# SNES_DRONE_CART.net
KiCad netlist of a schematic drawn in Altium Designer
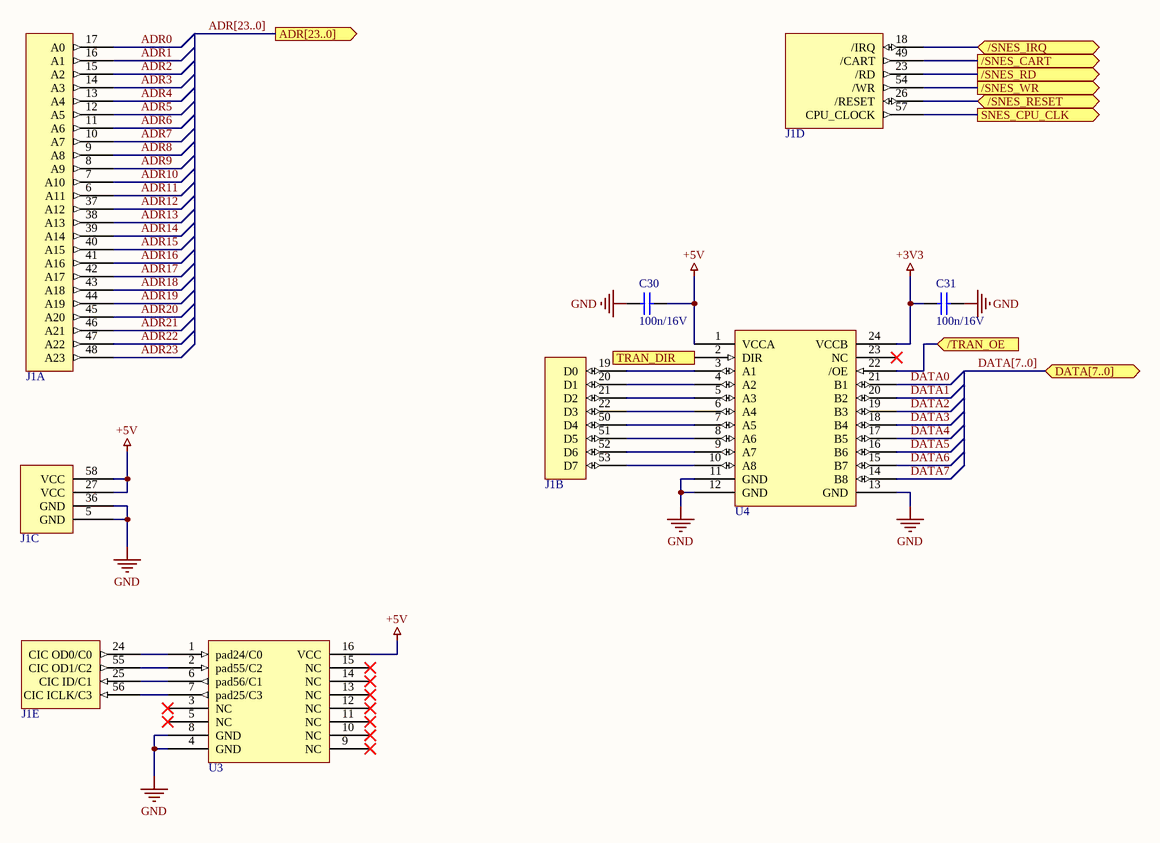
[diagram p0: SNES_DRONE_CART.SchDoc]

(export (version "E")
  (design (tool "Eeschema 10.0.6"))
  (components
    (comp (ref "C30")
      (value "100n/16V")
      (footprint "0402_RES")
      (description "Keramikvielschichtkondensator, SMD, 0.1 µF, 16 V, 0402 [Metrisch 1005], ± 10%, X5R, Baureihe MC")
      (libsource (lib "My_Integrated_Library") (part "Cap_100n_0402"))
    )
    (comp (ref "C31")
      (value "100n/16V")
      (footprint "0402_RES")
      (description "Keramikvielschichtkondensator, SMD, 0.1 µF, 16 V, 0402 [Metrisch 1005], ± 10%, X5R, Baureihe MC")
      (libsource (lib "My_Integrated_Library") (part "Cap_100n_0402"))
    )
    (comp (ref "J1")
      (value "SNES Cartridge Connector")
      (footprint "SNES Cartridge Connector")
      (libsource (lib "My_Schlib") (part "SNES Cartridge Connector"))
    )
    (comp (ref "U3")
      (value "IC_D411A")
      (footprint "DIP16")
      (description "SNES CIC Chip")
      (libsource (lib "My_Integrated_Library") (part "IC_D411A"))
    )
    (comp (ref "U4")
      (value "IC_SN74LVCC3245APWR")
      (footprint "TSSOP24")
      (description "Bus-Transceiver, Produktreihe LVC, 8 Eingänge, 50mA, 7ns, 2.3V bis 5.5V, TSSOP 24")
      (libsource (lib "My_Schlib") (part "IC_SN74LVCC3245APWR"))
    )
  )
  (nets
    (net (code "1") (name "+3V3") (class "Default")
      (node (ref "C31") (pin "1") (pinfunction "1_1") (pintype "passive"))
      (node (ref "U4") (pin "24") (pinfunction "VCCB_24") (pintype "power_in"))
    )
    (net (code "2") (name "+5V") (class "Default")
      (node (ref "C30") (pin "2") (pinfunction "2_2") (pintype "passive"))
      (node (ref "J1") (pin "27") (pinfunction "VCC_27") (pintype "power_in"))
      (node (ref "J1") (pin "58") (pinfunction "VCC_58") (pintype "power_in"))
      (node (ref "U3") (pin "16") (pinfunction "VCC_16") (pintype "power_in"))
      (node (ref "U4") (pin "1") (pinfunction "VCCA_1") (pintype "power_in"))
    )
    (net (code "3") (name "/ADR0") (class "Default")
      (node (ref "J1") (pin "17") (pinfunction "A0_17") (pintype "output"))
    )
    (net (code "4") (name "/ADR1") (class "Default")
      (node (ref "J1") (pin "16") (pinfunction "A1_16") (pintype "output"))
    )
    (net (code "5") (name "/ADR2") (class "Default")
      (node (ref "J1") (pin "15") (pinfunction "A2_15") (pintype "output"))
    )
    (net (code "6") (name "/ADR3") (class "Default")
      (node (ref "J1") (pin "14") (pinfunction "A3_14") (pintype "output"))
    )
    (net (code "7") (name "/ADR4") (class "Default")
      (node (ref "J1") (pin "13") (pinfunction "A4_13") (pintype "output"))
    )
    (net (code "8") (name "/ADR5") (class "Default")
      (node (ref "J1") (pin "12") (pinfunction "A5_12") (pintype "output"))
    )
    (net (code "9") (name "/ADR6") (class "Default")
      (node (ref "J1") (pin "11") (pinfunction "A6_11") (pintype "output"))
    )
    (net (code "10") (name "/ADR7") (class "Default")
      (node (ref "J1") (pin "10") (pinfunction "A7_10") (pintype "output"))
    )
    (net (code "11") (name "/ADR8") (class "Default")
      (node (ref "J1") (pin "9") (pinfunction "A8_9") (pintype "output"))
    )
    (net (code "12") (name "/ADR9") (class "Default")
      (node (ref "J1") (pin "8") (pinfunction "A9_8") (pintype "output"))
    )
    (net (code "13") (name "/ADR10") (class "Default")
      (node (ref "J1") (pin "7") (pinfunction "A10_7") (pintype "output"))
    )
    (net (code "14") (name "/ADR11") (class "Default")
      (node (ref "J1") (pin "6") (pinfunction "A11_6") (pintype "output"))
    )
    (net (code "15") (name "/ADR12") (class "Default")
      (node (ref "J1") (pin "37") (pinfunction "A12_37") (pintype "output"))
    )
    (net (code "16") (name "/ADR13") (class "Default")
      (node (ref "J1") (pin "38") (pinfunction "A13_38") (pintype "output"))
    )
    (net (code "17") (name "/ADR14") (class "Default")
      (node (ref "J1") (pin "39") (pinfunction "A14_39") (pintype "output"))
    )
    (net (code "18") (name "/ADR15") (class "Default")
      (node (ref "J1") (pin "40") (pinfunction "A15_40") (pintype "output"))
    )
    (net (code "19") (name "/ADR16") (class "Default")
      (node (ref "J1") (pin "41") (pinfunction "A16_41") (pintype "output"))
    )
    (net (code "20") (name "/ADR17") (class "Default")
      (node (ref "J1") (pin "42") (pinfunction "A17_42") (pintype "output"))
    )
    (net (code "21") (name "/ADR18") (class "Default")
      (node (ref "J1") (pin "43") (pinfunction "A18_43") (pintype "output"))
    )
    (net (code "22") (name "/ADR19") (class "Default")
      (node (ref "J1") (pin "44") (pinfunction "A19_44") (pintype "output"))
    )
    (net (code "23") (name "/ADR20") (class "Default")
      (node (ref "J1") (pin "45") (pinfunction "A20_45") (pintype "output"))
    )
    (net (code "24") (name "/ADR21") (class "Default")
      (node (ref "J1") (pin "46") (pinfunction "A21_46") (pintype "output"))
    )
    (net (code "25") (name "/ADR22") (class "Default")
      (node (ref "J1") (pin "47") (pinfunction "A22_47") (pintype "output"))
    )
    (net (code "26") (name "/ADR23") (class "Default")
      (node (ref "J1") (pin "48") (pinfunction "A23_48") (pintype "output"))
    )
    (net (code "28") (name "/DATA0") (class "Default")
      (node (ref "U4") (pin "21") (pinfunction "B1_21") (pintype "bidirectional"))
    )
    (net (code "29") (name "/DATA1") (class "Default")
      (node (ref "U4") (pin "20") (pinfunction "B2_20") (pintype "bidirectional"))
    )
    (net (code "30") (name "/DATA2") (class "Default")
      (node (ref "U4") (pin "19") (pinfunction "B3_19") (pintype "bidirectional"))
    )
    (net (code "31") (name "/DATA3") (class "Default")
      (node (ref "U4") (pin "18") (pinfunction "B4_18") (pintype "bidirectional"))
    )
    (net (code "32") (name "/DATA4") (class "Default")
      (node (ref "U4") (pin "17") (pinfunction "B5_17") (pintype "bidirectional"))
    )
    (net (code "33") (name "/DATA5") (class "Default")
      (node (ref "U4") (pin "16") (pinfunction "B6_16") (pintype "bidirectional"))
    )
    (net (code "34") (name "/DATA6") (class "Default")
      (node (ref "U4") (pin "15") (pinfunction "B7_15") (pintype "bidirectional"))
    )
    (net (code "35") (name "/DATA7") (class "Default")
      (node (ref "U4") (pin "14") (pinfunction "B8_14") (pintype "bidirectional"))
    )
    (net (code "37") (name "/SNES_CPU_CLK") (class "Default")
      (node (ref "J1") (pin "57") (pinfunction "CPU_CLOCK_57") (pintype "output"))
    )
    (net (code "38") (name "/TRAN_DIR") (class "Default")
      (node (ref "U4") (pin "2") (pinfunction "DIR_2") (pintype "input"))
    )
    (net (code "39") (name "/{slash}SNES_CART") (class "Default")
      (node (ref "J1") (pin "49") (pinfunction "/CART_49") (pintype "output"))
    )
    (net (code "40") (name "/{slash}SNES_IRQ") (class "Default")
      (node (ref "J1") (pin "18") (pinfunction "/IRQ_18") (pintype "bidirectional"))
    )
    (net (code "41") (name "/{slash}SNES_RD") (class "Default")
      (node (ref "J1") (pin "23") (pinfunction "/RD_23") (pintype "output"))
    )
    (net (code "42") (name "/{slash}SNES_RESET") (class "Default")
      (node (ref "J1") (pin "26") (pinfunction "/RESET_26") (pintype "bidirectional"))
    )
    (net (code "43") (name "/{slash}SNES_WR") (class "Default")
      (node (ref "J1") (pin "54") (pinfunction "/WR_54") (pintype "output"))
    )
    (net (code "44") (name "/{slash}TRAN_OE") (class "Default")
      (node (ref "U4") (pin "22") (pinfunction "/OE_22") (pintype "input"))
    )
    (net (code "45") (name "GND") (class "Default")
      (node (ref "C30") (pin "1") (pinfunction "1_1") (pintype "passive"))
      (node (ref "C31") (pin "2") (pinfunction "2_2") (pintype "passive"))
      (node (ref "J1") (pin "36") (pinfunction "GND_36") (pintype "power_in"))
      (node (ref "J1") (pin "5") (pinfunction "GND_5") (pintype "power_in"))
      (node (ref "U3") (pin "4") (pinfunction "GND_4") (pintype "power_in"))
      (node (ref "U3") (pin "8") (pinfunction "GND_8") (pintype "power_in"))
      (node (ref "U4") (pin "11") (pinfunction "GND_11") (pintype "power_in"))
      (node (ref "U4") (pin "12") (pinfunction "GND_12") (pintype "power_in"))
      (node (ref "U4") (pin "13") (pinfunction "GND_13") (pintype "power_in"))
    )
    (net (code "46") (name "Net-(J1B-D0)") (class "Default")
      (node (ref "J1") (pin "19") (pinfunction "D0_19") (pintype "bidirectional"))
      (node (ref "U4") (pin "3") (pinfunction "A1_3") (pintype "bidirectional"))
    )
    (net (code "47") (name "Net-(J1B-D1)") (class "Default")
      (node (ref "J1") (pin "20") (pinfunction "D1_20") (pintype "bidirectional"))
      (node (ref "U4") (pin "4") (pinfunction "A2_4") (pintype "bidirectional"))
    )
    (net (code "48") (name "Net-(J1B-D2)") (class "Default")
      (node (ref "J1") (pin "21") (pinfunction "D2_21") (pintype "bidirectional"))
      (node (ref "U4") (pin "5") (pinfunction "A3_5") (pintype "bidirectional"))
    )
    (net (code "49") (name "Net-(J1B-D3)") (class "Default")
      (node (ref "J1") (pin "22") (pinfunction "D3_22") (pintype "bidirectional"))
      (node (ref "U4") (pin "6") (pinfunction "A4_6") (pintype "bidirectional"))
    )
    (net (code "50") (name "Net-(J1B-D4)") (class "Default")
      (node (ref "J1") (pin "50") (pinfunction "D4_50") (pintype "bidirectional"))
      (node (ref "U4") (pin "7") (pinfunction "A5_7") (pintype "bidirectional"))
    )
    (net (code "51") (name "Net-(J1B-D5)") (class "Default")
      (node (ref "J1") (pin "51") (pinfunction "D5_51") (pintype "bidirectional"))
      (node (ref "U4") (pin "8") (pinfunction "A6_8") (pintype "bidirectional"))
    )
    (net (code "52") (name "Net-(J1B-D6)") (class "Default")
      (node (ref "J1") (pin "52") (pinfunction "D6_52") (pintype "bidirectional"))
      (node (ref "U4") (pin "9") (pinfunction "A7_9") (pintype "bidirectional"))
    )
    (net (code "53") (name "Net-(J1B-D7)") (class "Default")
      (node (ref "J1") (pin "53") (pinfunction "D7_53") (pintype "bidirectional"))
      (node (ref "U4") (pin "10") (pinfunction "A8_10") (pintype "bidirectional"))
    )
    (net (code "54") (name "Net-(J1E-CIC_ICLK{slash}C3)") (class "Default")
      (node (ref "J1") (pin "56") (pinfunction "CIC_ICLK/C3_56") (pintype "input"))
      (node (ref "U3") (pin "7") (pinfunction "pad25/C3_7") (pintype "output"))
    )
    (net (code "55") (name "Net-(J1E-CIC_ID{slash}C1)") (class "Default")
      (node (ref "J1") (pin "25") (pinfunction "CIC_ID/C1_25") (pintype "input"))
      (node (ref "U3") (pin "6") (pinfunction "pad56/C1_6") (pintype "output"))
    )
    (net (code "56") (name "Net-(J1E-CIC_OD0{slash}C0)") (class "Default")
      (node (ref "J1") (pin "24") (pinfunction "CIC_OD0/C0_24") (pintype "output"))
      (node (ref "U3") (pin "1") (pinfunction "pad24/C0_1") (pintype "input"))
    )
    (net (code "57") (name "Net-(J1E-CIC_OD1{slash}C2)") (class "Default")
      (node (ref "J1") (pin "55") (pinfunction "CIC_OD1/C2_55") (pintype "output"))
      (node (ref "U3") (pin "2") (pinfunction "pad55/C2_2") (pintype "input"))
    )
    (net (code "58") (name "unconnected-(U3-NC-Pad3)") (class "Default")
      (node (ref "U3") (pin "3") (pinfunction "NC_3") (pintype "power_in+no_connect"))
    )
    (net (code "59") (name "unconnected-(U3-NC-Pad5)") (class "Default")
      (node (ref "U3") (pin "5") (pinfunction "NC_5") (pintype "power_in+no_connect"))
    )
    (net (code "60") (name "unconnected-(U3-NC-Pad9)") (class "Default")
      (node (ref "U3") (pin "9") (pinfunction "NC_9") (pintype "power_in+no_connect"))
    )
    (net (code "61") (name "unconnected-(U3-NC-Pad10)") (class "Default")
      (node (ref "U3") (pin "10") (pinfunction "NC_10") (pintype "power_in+no_connect"))
    )
    (net (code "62") (name "unconnected-(U3-NC-Pad11)") (class "Default")
      (node (ref "U3") (pin "11") (pinfunction "NC_11") (pintype "power_in+no_connect"))
    )
    (net (code "63") (name "unconnected-(U3-NC-Pad12)") (class "Default")
      (node (ref "U3") (pin "12") (pinfunction "NC_12") (pintype "power_in+no_connect"))
    )
    (net (code "64") (name "unconnected-(U3-NC-Pad13)") (class "Default")
      (node (ref "U3") (pin "13") (pinfunction "NC_13") (pintype "power_in+no_connect"))
    )
    (net (code "65") (name "unconnected-(U3-NC-Pad14)") (class "Default")
      (node (ref "U3") (pin "14") (pinfunction "NC_14") (pintype "power_in+no_connect"))
    )
    (net (code "66") (name "unconnected-(U3-NC-Pad15)") (class "Default")
      (node (ref "U3") (pin "15") (pinfunction "NC_15") (pintype "power_in+no_connect"))
    )
    (net (code "67") (name "unconnected-(U4-NC-Pad23)") (class "Default")
      (node (ref "U4") (pin "23") (pinfunction "NC_23") (pintype "passive+no_connect"))
    )
  )
)
